# Memory.net
KiCad netlist of a schematic drawn in Altium Designer
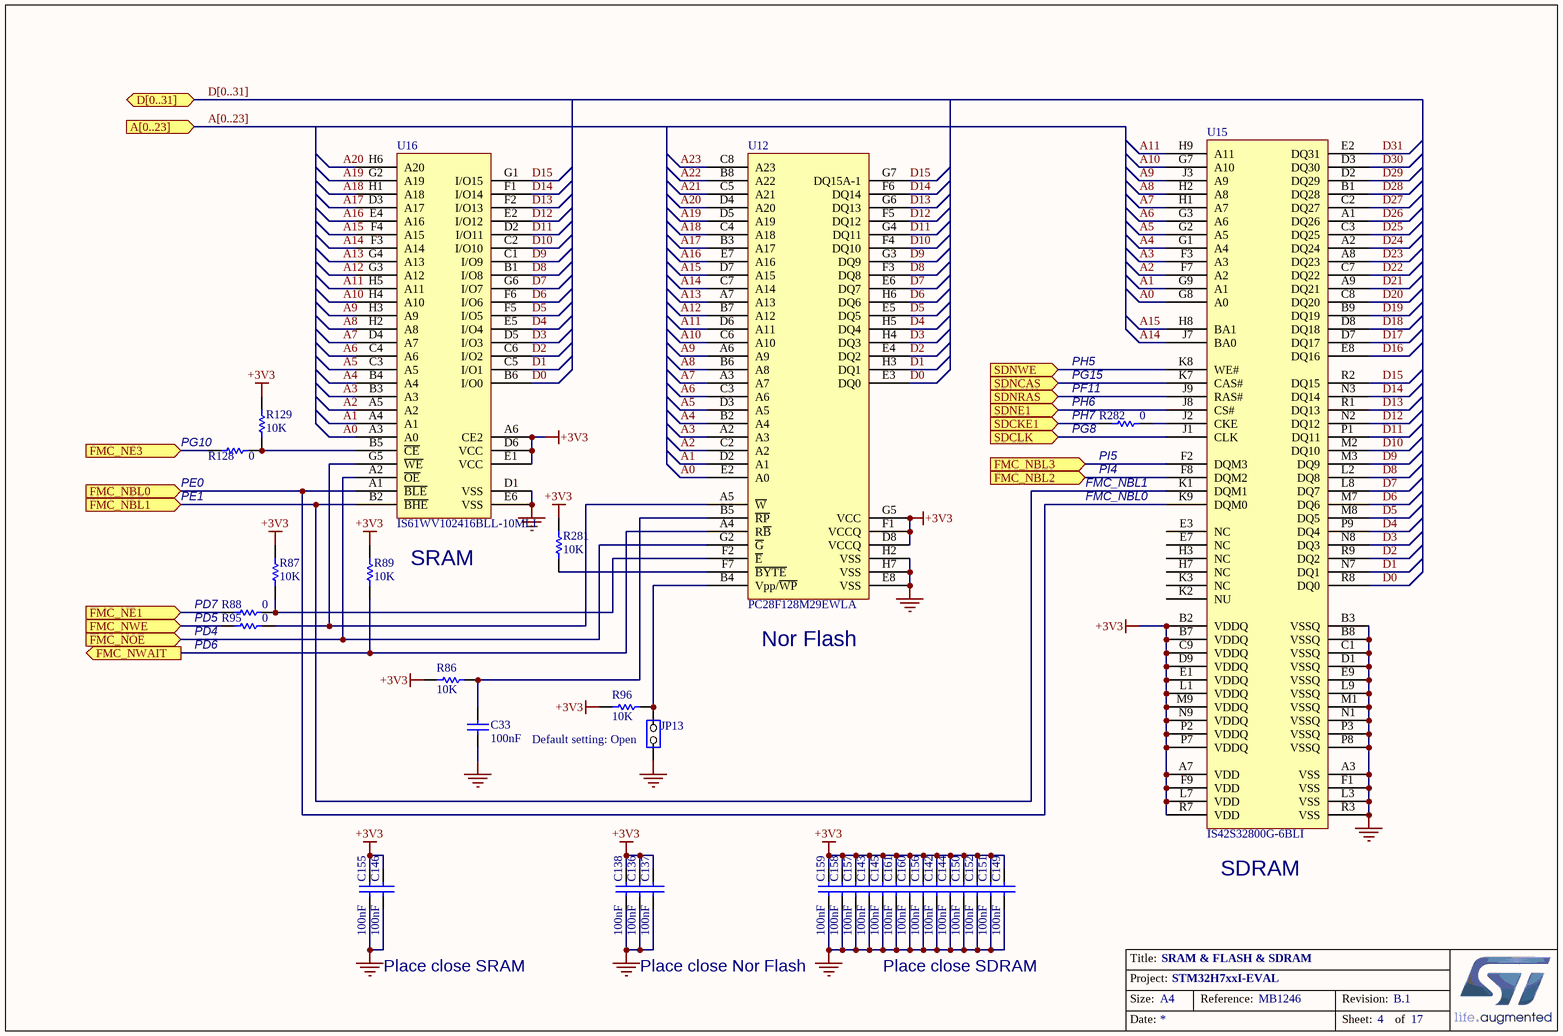
[diagram p0: Memory.SchDoc]

(export (version "E")
  (design (tool "Eeschema 10.0.6"))
  (components
    (comp (ref "C33")
      (value "100nF")
      (footprint "0603C")
      (description "Capacitor")
      (fields (field (name "PUBLISHER") "Altium Limited"))
      (libsource (lib "Miscellaneous Devices") (part "Cap"))
    )
    (comp (ref "C136")
      (value "100nF")
      (footprint "0603C")
      (description "Capacitor")
      (fields (field (name "PUBLISHER") "Altium Limited"))
      (libsource (lib "Miscellaneous Devices") (part "Cap"))
    )
    (comp (ref "C137")
      (value "100nF")
      (footprint "0603C")
      (description "Capacitor")
      (fields (field (name "PUBLISHER") "Altium Limited"))
      (libsource (lib "Miscellaneous Devices") (part "Cap"))
    )
    (comp (ref "C138")
      (value "100nF")
      (footprint "0603C")
      (description "Capacitor")
      (fields (field (name "PUBLISHER") "Altium Limited"))
      (libsource (lib "Miscellaneous Devices") (part "Cap"))
    )
    (comp (ref "C142")
      (value "100nF")
      (footprint "0603C")
      (description "Capacitor")
      (fields (field (name "PUBLISHER") "Altium Limited"))
      (libsource (lib "Miscellaneous Devices") (part "Cap"))
    )
    (comp (ref "C143")
      (value "100nF")
      (footprint "0603C")
      (description "Capacitor")
      (fields (field (name "PUBLISHER") "Altium Limited"))
      (libsource (lib "Miscellaneous Devices") (part "Cap"))
    )
    (comp (ref "C144")
      (value "100nF")
      (footprint "0603C")
      (description "Capacitor")
      (fields (field (name "PUBLISHER") "Altium Limited"))
      (libsource (lib "Miscellaneous Devices") (part "Cap"))
    )
    (comp (ref "C145")
      (value "100nF")
      (footprint "0603C")
      (description "Capacitor")
      (fields (field (name "PUBLISHER") "Altium Limited"))
      (libsource (lib "Miscellaneous Devices") (part "Cap"))
    )
    (comp (ref "C146")
      (value "100nF")
      (footprint "0603C")
      (description "Capacitor")
      (fields (field (name "PUBLISHER") "Altium Limited"))
      (libsource (lib "Miscellaneous Devices") (part "Cap"))
    )
    (comp (ref "C149")
      (value "100nF")
      (footprint "0603C")
      (description "Capacitor")
      (fields (field (name "PUBLISHER") "Altium Limited"))
      (libsource (lib "Miscellaneous Devices") (part "Cap"))
    )
    (comp (ref "C150")
      (value "100nF")
      (footprint "0603C")
      (description "Capacitor")
      (fields (field (name "PUBLISHER") "Altium Limited"))
      (libsource (lib "Miscellaneous Devices") (part "Cap"))
    )
    (comp (ref "C151")
      (value "100nF")
      (footprint "0603C")
      (description "Capacitor")
      (fields (field (name "PUBLISHER") "Altium Limited"))
      (libsource (lib "Miscellaneous Devices") (part "Cap"))
    )
    (comp (ref "C152")
      (value "100nF")
      (footprint "0603C")
      (description "Capacitor")
      (fields (field (name "PUBLISHER") "Altium Limited"))
      (libsource (lib "Miscellaneous Devices") (part "Cap"))
    )
    (comp (ref "C155")
      (value "100nF")
      (footprint "0603C")
      (description "Capacitor")
      (fields (field (name "PUBLISHER") "Altium Limited"))
      (libsource (lib "Miscellaneous Devices") (part "Cap"))
    )
    (comp (ref "C156")
      (value "100nF")
      (footprint "0603C")
      (description "Capacitor")
      (fields (field (name "PUBLISHER") "Altium Limited"))
      (libsource (lib "Miscellaneous Devices") (part "Cap"))
    )
    (comp (ref "C157")
      (value "100nF")
      (footprint "0603C")
      (description "Capacitor")
      (fields (field (name "PUBLISHER") "Altium Limited"))
      (libsource (lib "Miscellaneous Devices") (part "Cap"))
    )
    (comp (ref "C158")
      (value "100nF")
      (footprint "0603C")
      (description "Capacitor")
      (fields (field (name "PUBLISHER") "Altium Limited"))
      (libsource (lib "Miscellaneous Devices") (part "Cap"))
    )
    (comp (ref "C159")
      (value "100nF")
      (footprint "0603C")
      (description "Capacitor")
      (fields (field (name "PUBLISHER") "Altium Limited"))
      (libsource (lib "Miscellaneous Devices") (part "Cap"))
    )
    (comp (ref "C160")
      (value "100nF")
      (footprint "0603C")
      (description "Capacitor")
      (fields (field (name "PUBLISHER") "Altium Limited"))
      (libsource (lib "Miscellaneous Devices") (part "Cap"))
    )
    (comp (ref "C161")
      (value "100nF")
      (footprint "0603C")
      (description "Capacitor")
      (fields (field (name "PUBLISHER") "Altium Limited"))
      (libsource (lib "Miscellaneous Devices") (part "Cap"))
    )
    (comp (ref "JP13") (value "~") (footprint "SIP2") (libsource (lib "*") (part "JP2")))
    (comp (ref "R86")
      (value "10K")
      (footprint "0603R")
      (description "Resistor")
      (fields (field (name "PUBLISHER") "Altium Limited"))
      (libsource (lib "Miscellaneous Devices") (part "Res1"))
    )
    (comp (ref "R87")
      (value "10K")
      (footprint "0603R")
      (description "Resistor")
      (fields (field (name "PUBLISHER") "Altium Limited"))
      (libsource (lib "Miscellaneous Devices") (part "Res1"))
    )
    (comp (ref "R88")
      (value "0")
      (footprint "0603R")
      (description "Resistor")
      (fields (field (name "PUBLISHER") "Altium Limited"))
      (libsource (lib "Miscellaneous Devices") (part "Res1"))
    )
    (comp (ref "R89")
      (value "10K")
      (footprint "0603R")
      (description "Resistor")
      (fields (field (name "PUBLISHER") "Altium Limited"))
      (libsource (lib "Miscellaneous Devices") (part "Res1"))
    )
    (comp (ref "R95")
      (value "0")
      (footprint "0603R")
      (description "Resistor")
      (fields (field (name "PUBLISHER") "Altium Limited"))
      (libsource (lib "Miscellaneous Devices") (part "Res1"))
    )
    (comp (ref "R96")
      (value "10K")
      (footprint "0603R")
      (description "Resistor")
      (fields (field (name "PUBLISHER") "Altium Limited"))
      (libsource (lib "Miscellaneous Devices") (part "Res1"))
    )
    (comp (ref "R128")
      (value "0")
      (footprint "0603R")
      (description "Resistor")
      (fields (field (name "PUBLISHER") "Altium Limited"))
      (libsource (lib "Miscellaneous Devices") (part "Res1"))
    )
    (comp (ref "R129")
      (value "10K")
      (footprint "0603R")
      (description "Resistor")
      (fields (field (name "PUBLISHER") "Altium Limited"))
      (libsource (lib "Miscellaneous Devices") (part "Res1"))
    )
    (comp (ref "R281")
      (value "10K")
      (footprint "0603R")
      (description "Resistor")
      (fields (field (name "PUBLISHER") "Altium Limited"))
      (libsource (lib "Miscellaneous Devices") (part "Res1"))
    )
    (comp (ref "R282")
      (value "0")
      (footprint "0603R")
      (description "Resistor")
      (fields (field (name "PUBLISHER") "Altium Limited"))
      (libsource (lib "Miscellaneous Devices") (part "Res1"))
    )
    (comp (ref "U12")
      (value "PC28F128M29EWLA")
      (footprint "FBGA64_1_11X13")
      (libsource (lib "MB964") (part "M29W128FL70ZA6E"))
    )
    (comp (ref "U15")
      (value "IS42S32800G-6BLI")
      (footprint "FBGA90_0R8_8X13")
      (libsource (lib "mb1045") (part "MT48LC4M32B2B5"))
    )
    (comp (ref "U16")
      (value "IS61WV102416BLL-10MLI")
      (footprint "BGA48_0R75_9X11")
      (libsource (lib "MB901") (part "IS61WV102416BLL-10MLI"))
    )
  )
  (nets
    (net (code "1") (name "+3V3") (class "Default")
      (node (ref "C136") (pin "1") (pinfunction "1_1") (pintype "passive"))
      (node (ref "C137") (pin "1") (pinfunction "1_1") (pintype "passive"))
      (node (ref "C138") (pin "1") (pinfunction "1_1") (pintype "passive"))
      (node (ref "C142") (pin "1") (pinfunction "1_1") (pintype "passive"))
      (node (ref "C143") (pin "1") (pinfunction "1_1") (pintype "passive"))
      (node (ref "C144") (pin "1") (pinfunction "1_1") (pintype "passive"))
      (node (ref "C145") (pin "1") (pinfunction "1_1") (pintype "passive"))
      (node (ref "C146") (pin "1") (pinfunction "1_1") (pintype "passive"))
      (node (ref "C149") (pin "1") (pinfunction "1_1") (pintype "passive"))
      (node (ref "C150") (pin "1") (pinfunction "1_1") (pintype "passive"))
      (node (ref "C151") (pin "1") (pinfunction "1_1") (pintype "passive"))
      (node (ref "C152") (pin "1") (pinfunction "1_1") (pintype "passive"))
      (node (ref "C155") (pin "1") (pinfunction "1_1") (pintype "passive"))
      (node (ref "C156") (pin "1") (pinfunction "1_1") (pintype "passive"))
      (node (ref "C157") (pin "1") (pinfunction "1_1") (pintype "passive"))
      (node (ref "C158") (pin "1") (pinfunction "1_1") (pintype "passive"))
      (node (ref "C159") (pin "1") (pinfunction "1_1") (pintype "passive"))
      (node (ref "C160") (pin "1") (pinfunction "1_1") (pintype "passive"))
      (node (ref "C161") (pin "1") (pinfunction "1_1") (pintype "passive"))
      (node (ref "R129") (pin "2") (pinfunction "2_2") (pintype "passive"))
      (node (ref "R281") (pin "2") (pinfunction "2_2") (pintype "passive"))
      (node (ref "R86") (pin "1") (pinfunction "1_1") (pintype "passive"))
      (node (ref "R87") (pin "2") (pinfunction "2_2") (pintype "passive"))
      (node (ref "R89") (pin "2") (pinfunction "2_2") (pintype "passive"))
      (node (ref "R96") (pin "2") (pinfunction "2_2") (pintype "passive"))
      (node (ref "U12") (pin "D8") (pinfunction "VCCQ_D8") (pintype "passive"))
      (node (ref "U12") (pin "F1") (pinfunction "VCCQ_F1") (pintype "passive"))
      (node (ref "U12") (pin "G5") (pinfunction "VCC_G5") (pintype "passive"))
      (node (ref "U15") (pin "A7") (pinfunction "VDD_A7") (pintype "passive"))
      (node (ref "U15") (pin "B2") (pinfunction "VDDQ_B2") (pintype "passive"))
      (node (ref "U15") (pin "B7") (pinfunction "VDDQ_B7") (pintype "passive"))
      (node (ref "U15") (pin "C9") (pinfunction "VDDQ_C9") (pintype "passive"))
      (node (ref "U15") (pin "D9") (pinfunction "VDDQ_D9") (pintype "passive"))
      (node (ref "U15") (pin "E1") (pinfunction "VDDQ_E1") (pintype "passive"))
      (node (ref "U15") (pin "F9") (pinfunction "VDD_F9") (pintype "passive"))
      (node (ref "U15") (pin "L1") (pinfunction "VDDQ_L1") (pintype "passive"))
      (node (ref "U15") (pin "L7") (pinfunction "VDD_L7") (pintype "passive"))
      (node (ref "U15") (pin "M9") (pinfunction "VDDQ_M9") (pintype "passive"))
      (node (ref "U15") (pin "N9") (pinfunction "VDDQ_N9") (pintype "passive"))
      (node (ref "U15") (pin "P2") (pinfunction "VDDQ_P2") (pintype "passive"))
      (node (ref "U15") (pin "P7") (pinfunction "VDDQ_P7") (pintype "passive"))
      (node (ref "U15") (pin "R7") (pinfunction "VDD_R7") (pintype "passive"))
      (node (ref "U16") (pin "A6") (pinfunction "CE2_A6") (pintype "passive"))
      (node (ref "U16") (pin "D6") (pinfunction "VCC_D6") (pintype "passive"))
      (node (ref "U16") (pin "E1") (pinfunction "VCC_E1") (pintype "passive"))
    )
    (net (code "2") (name "/A0") (class "Default")
      (node (ref "U12") (pin "E2") (pinfunction "A0_E2") (pintype "passive"))
      (node (ref "U15") (pin "G8") (pinfunction "A0_G8") (pintype "passive"))
      (node (ref "U16") (pin "A3") (pinfunction "A0_A3") (pintype "passive"))
    )
    (net (code "3") (name "/A1") (class "Default")
      (node (ref "U12") (pin "D2") (pinfunction "A1_D2") (pintype "passive"))
      (node (ref "U15") (pin "G9") (pinfunction "A1_G9") (pintype "passive"))
      (node (ref "U16") (pin "A4") (pinfunction "A1_A4") (pintype "passive"))
    )
    (net (code "4") (name "/A2") (class "Default")
      (node (ref "U12") (pin "C2") (pinfunction "A2_C2") (pintype "passive"))
      (node (ref "U15") (pin "F7") (pinfunction "A2_F7") (pintype "passive"))
      (node (ref "U16") (pin "A5") (pinfunction "A2_A5") (pintype "passive"))
    )
    (net (code "5") (name "/A3") (class "Default")
      (node (ref "U12") (pin "A2") (pinfunction "A3_A2") (pintype "passive"))
      (node (ref "U15") (pin "F3") (pinfunction "A3_F3") (pintype "passive"))
      (node (ref "U16") (pin "B3") (pinfunction "A3_B3") (pintype "passive"))
    )
    (net (code "6") (name "/A4") (class "Default")
      (node (ref "U12") (pin "B2") (pinfunction "A4_B2") (pintype "passive"))
      (node (ref "U15") (pin "G1") (pinfunction "A4_G1") (pintype "passive"))
      (node (ref "U16") (pin "B4") (pinfunction "A4_B4") (pintype "passive"))
    )
    (net (code "7") (name "/A5") (class "Default")
      (node (ref "U12") (pin "D3") (pinfunction "A5_D3") (pintype "passive"))
      (node (ref "U15") (pin "G2") (pinfunction "A5_G2") (pintype "passive"))
      (node (ref "U16") (pin "C3") (pinfunction "A5_C3") (pintype "passive"))
    )
    (net (code "8") (name "/A6") (class "Default")
      (node (ref "U12") (pin "C3") (pinfunction "A6_C3") (pintype "passive"))
      (node (ref "U15") (pin "G3") (pinfunction "A6_G3") (pintype "passive"))
      (node (ref "U16") (pin "C4") (pinfunction "A6_C4") (pintype "passive"))
    )
    (net (code "9") (name "/A7") (class "Default")
      (node (ref "U12") (pin "A3") (pinfunction "A7_A3") (pintype "passive"))
      (node (ref "U15") (pin "H1") (pinfunction "A7_H1") (pintype "passive"))
      (node (ref "U16") (pin "D4") (pinfunction "A7_D4") (pintype "passive"))
    )
    (net (code "10") (name "/A8") (class "Default")
      (node (ref "U12") (pin "B6") (pinfunction "A8_B6") (pintype "passive"))
      (node (ref "U15") (pin "H2") (pinfunction "A8_H2") (pintype "passive"))
      (node (ref "U16") (pin "H2") (pinfunction "A8_H2") (pintype "passive"))
    )
    (net (code "11") (name "/A9") (class "Default")
      (node (ref "U12") (pin "A6") (pinfunction "A9_A6") (pintype "passive"))
      (node (ref "U15") (pin "J3") (pinfunction "A9_J3") (pintype "passive"))
      (node (ref "U16") (pin "H3") (pinfunction "A9_H3") (pintype "passive"))
    )
    (net (code "12") (name "/A10") (class "Default")
      (node (ref "U12") (pin "C6") (pinfunction "A10_C6") (pintype "passive"))
      (node (ref "U15") (pin "G7") (pinfunction "A10_G7") (pintype "passive"))
      (node (ref "U16") (pin "H4") (pinfunction "A10_H4") (pintype "passive"))
    )
    (net (code "13") (name "/A11") (class "Default")
      (node (ref "U12") (pin "D6") (pinfunction "A11_D6") (pintype "passive"))
      (node (ref "U15") (pin "H9") (pinfunction "A11_H9") (pintype "passive"))
      (node (ref "U16") (pin "H5") (pinfunction "A11_H5") (pintype "passive"))
    )
    (net (code "14") (name "/A12") (class "Default")
      (node (ref "U12") (pin "B7") (pinfunction "A12_B7") (pintype "passive"))
      (node (ref "U16") (pin "G3") (pinfunction "A12_G3") (pintype "passive"))
    )
    (net (code "15") (name "/A13") (class "Default")
      (node (ref "U12") (pin "A7") (pinfunction "A13_A7") (pintype "passive"))
      (node (ref "U16") (pin "G4") (pinfunction "A13_G4") (pintype "passive"))
    )
    (net (code "16") (name "/A14") (class "Default")
      (node (ref "U12") (pin "C7") (pinfunction "A14_C7") (pintype "passive"))
      (node (ref "U15") (pin "J7") (pinfunction "BA0_J7") (pintype "passive"))
      (node (ref "U16") (pin "F3") (pinfunction "A14_F3") (pintype "passive"))
    )
    (net (code "17") (name "/A15") (class "Default")
      (node (ref "U12") (pin "D7") (pinfunction "A15_D7") (pintype "passive"))
      (node (ref "U15") (pin "H8") (pinfunction "BA1_H8") (pintype "passive"))
      (node (ref "U16") (pin "F4") (pinfunction "A15_F4") (pintype "passive"))
    )
    (net (code "18") (name "/A16") (class "Default")
      (node (ref "U12") (pin "E7") (pinfunction "A16_E7") (pintype "passive"))
      (node (ref "U16") (pin "E4") (pinfunction "A16_E4") (pintype "passive"))
    )
    (net (code "19") (name "/A17") (class "Default")
      (node (ref "U12") (pin "B3") (pinfunction "A17_B3") (pintype "passive"))
      (node (ref "U16") (pin "D3") (pinfunction "A17_D3") (pintype "passive"))
    )
    (net (code "20") (name "/A18") (class "Default")
      (node (ref "U12") (pin "C4") (pinfunction "A18_C4") (pintype "passive"))
      (node (ref "U16") (pin "H1") (pinfunction "A18_H1") (pintype "passive"))
    )
    (net (code "21") (name "/A19") (class "Default")
      (node (ref "U12") (pin "D5") (pinfunction "A19_D5") (pintype "passive"))
      (node (ref "U16") (pin "G2") (pinfunction "A19_G2") (pintype "passive"))
    )
    (net (code "22") (name "/A20") (class "Default")
      (node (ref "U12") (pin "D4") (pinfunction "A20_D4") (pintype "passive"))
      (node (ref "U16") (pin "H6") (pinfunction "A20_H6") (pintype "passive"))
    )
    (net (code "23") (name "/A21") (class "Default")
      (node (ref "U12") (pin "C5") (pinfunction "A21_C5") (pintype "passive"))
    )
    (net (code "24") (name "/A22") (class "Default")
      (node (ref "U12") (pin "B8") (pinfunction "A22_B8") (pintype "passive"))
    )
    (net (code "25") (name "/A23") (class "Default")
      (node (ref "U12") (pin "C8") (pinfunction "A23_C8") (pintype "passive"))
    )
    (net (code "27") (name "/D0") (class "Default")
      (node (ref "U12") (pin "E3") (pinfunction "DQ0_E3") (pintype "passive"))
      (node (ref "U15") (pin "R8") (pinfunction "DQ0_R8") (pintype "passive"))
      (node (ref "U16") (pin "B6") (pinfunction "I/O0_B6") (pintype "passive"))
    )
    (net (code "28") (name "/D1") (class "Default")
      (node (ref "U12") (pin "H3") (pinfunction "DQ1_H3") (pintype "passive"))
      (node (ref "U15") (pin "N7") (pinfunction "DQ1_N7") (pintype "passive"))
      (node (ref "U16") (pin "C5") (pinfunction "I/O1_C5") (pintype "passive"))
    )
    (net (code "29") (name "/D2") (class "Default")
      (node (ref "U12") (pin "E4") (pinfunction "DQ2_E4") (pintype "passive"))
      (node (ref "U15") (pin "R9") (pinfunction "DQ2_R9") (pintype "passive"))
      (node (ref "U16") (pin "C6") (pinfunction "I/O2_C6") (pintype "passive"))
    )
    (net (code "30") (name "/D3") (class "Default")
      (node (ref "U12") (pin "H4") (pinfunction "DQ3_H4") (pintype "passive"))
      (node (ref "U15") (pin "N8") (pinfunction "DQ3_N8") (pintype "passive"))
      (node (ref "U16") (pin "D5") (pinfunction "I/O3_D5") (pintype "passive"))
    )
    (net (code "31") (name "/D4") (class "Default")
      (node (ref "U12") (pin "H5") (pinfunction "DQ4_H5") (pintype "passive"))
      (node (ref "U15") (pin "P9") (pinfunction "DQ4_P9") (pintype "passive"))
      (node (ref "U16") (pin "E5") (pinfunction "I/O4_E5") (pintype "passive"))
    )
    (net (code "32") (name "/D5") (class "Default")
      (node (ref "U12") (pin "E5") (pinfunction "DQ5_E5") (pintype "passive"))
      (node (ref "U15") (pin "M8") (pinfunction "DQ5_M8") (pintype "passive"))
      (node (ref "U16") (pin "F5") (pinfunction "I/O5_F5") (pintype "passive"))
    )
    (net (code "33") (name "/D6") (class "Default")
      (node (ref "U12") (pin "H6") (pinfunction "DQ6_H6") (pintype "passive"))
      (node (ref "U15") (pin "M7") (pinfunction "DQ6_M7") (pintype "passive"))
      (node (ref "U16") (pin "F6") (pinfunction "I/O6_F6") (pintype "passive"))
    )
    (net (code "34") (name "/D7") (class "Default")
      (node (ref "U12") (pin "E6") (pinfunction "DQ7_E6") (pintype "passive"))
      (node (ref "U15") (pin "L8") (pinfunction "DQ7_L8") (pintype "passive"))
      (node (ref "U16") (pin "G6") (pinfunction "I/O7_G6") (pintype "passive"))
    )
    (net (code "35") (name "/D8") (class "Default")
      (node (ref "U12") (pin "F3") (pinfunction "DQ8_F3") (pintype "passive"))
      (node (ref "U15") (pin "L2") (pinfunction "DQ8_L2") (pintype "passive"))
      (node (ref "U16") (pin "B1") (pinfunction "I/O8_B1") (pintype "passive"))
    )
    (net (code "36") (name "/D9") (class "Default")
      (node (ref "U12") (pin "G3") (pinfunction "DQ9_G3") (pintype "passive"))
      (node (ref "U15") (pin "M3") (pinfunction "DQ9_M3") (pintype "passive"))
      (node (ref "U16") (pin "C1") (pinfunction "I/O9_C1") (pintype "passive"))
    )
    (net (code "37") (name "/D10") (class "Default")
      (node (ref "U12") (pin "F4") (pinfunction "DQ10_F4") (pintype "passive"))
      (node (ref "U15") (pin "M2") (pinfunction "DQ10_M2") (pintype "passive"))
      (node (ref "U16") (pin "C2") (pinfunction "I/O10_C2") (pintype "passive"))
    )
    (net (code "38") (name "/D11") (class "Default")
      (node (ref "U12") (pin "G4") (pinfunction "DQ11_G4") (pintype "passive"))
      (node (ref "U15") (pin "P1") (pinfunction "DQ11_P1") (pintype "passive"))
      (node (ref "U16") (pin "D2") (pinfunction "I/O11_D2") (pintype "passive"))
    )
    (net (code "39") (name "/D12") (class "Default")
      (node (ref "U12") (pin "F5") (pinfunction "DQ12_F5") (pintype "passive"))
      (node (ref "U15") (pin "N2") (pinfunction "DQ12_N2") (pintype "passive"))
      (node (ref "U16") (pin "E2") (pinfunction "I/O12_E2") (pintype "passive"))
    )
    (net (code "40") (name "/D13") (class "Default")
      (node (ref "U12") (pin "G6") (pinfunction "DQ13_G6") (pintype "passive"))
      (node (ref "U15") (pin "R1") (pinfunction "DQ13_R1") (pintype "passive"))
      (node (ref "U16") (pin "F2") (pinfunction "I/O13_F2") (pintype "passive"))
    )
    (net (code "41") (name "/D14") (class "Default")
      (node (ref "U12") (pin "F6") (pinfunction "DQ14_F6") (pintype "passive"))
      (node (ref "U15") (pin "N3") (pinfunction "DQ14_N3") (pintype "passive"))
      (node (ref "U16") (pin "F1") (pinfunction "I/O14_F1") (pintype "passive"))
    )
    (net (code "42") (name "/D15") (class "Default")
      (node (ref "U12") (pin "G7") (pinfunction "DQ15A-1_G7") (pintype "passive"))
      (node (ref "U15") (pin "R2") (pinfunction "DQ15_R2") (pintype "passive"))
      (node (ref "U16") (pin "G1") (pinfunction "I/O15_G1") (pintype "passive"))
    )
    (net (code "43") (name "/D16") (class "Default")
      (node (ref "U15") (pin "E8") (pinfunction "DQ16_E8") (pintype "passive"))
    )
    (net (code "44") (name "/D17") (class "Default")
      (node (ref "U15") (pin "D7") (pinfunction "DQ17_D7") (pintype "passive"))
    )
    (net (code "45") (name "/D18") (class "Default")
      (node (ref "U15") (pin "D8") (pinfunction "DQ18_D8") (pintype "passive"))
    )
    (net (code "46") (name "/D19") (class "Default")
      (node (ref "U15") (pin "B9") (pinfunction "DQ19_B9") (pintype "passive"))
    )
    (net (code "47") (name "/D20") (class "Default")
      (node (ref "U15") (pin "C8") (pinfunction "DQ20_C8") (pintype "passive"))
    )
    (net (code "48") (name "/D21") (class "Default")
      (node (ref "U15") (pin "A9") (pinfunction "DQ21_A9") (pintype "passive"))
    )
    (net (code "49") (name "/D22") (class "Default")
      (node (ref "U15") (pin "C7") (pinfunction "DQ22_C7") (pintype "passive"))
    )
    (net (code "50") (name "/D23") (class "Default")
      (node (ref "U15") (pin "A8") (pinfunction "DQ23_A8") (pintype "passive"))
    )
    (net (code "51") (name "/D24") (class "Default")
      (node (ref "U15") (pin "A2") (pinfunction "DQ24_A2") (pintype "passive"))
    )
    (net (code "52") (name "/D25") (class "Default")
      (node (ref "U15") (pin "C3") (pinfunction "DQ25_C3") (pintype "passive"))
    )
    (net (code "53") (name "/D26") (class "Default")
      (node (ref "U15") (pin "A1") (pinfunction "DQ26_A1") (pintype "passive"))
    )
    (net (code "54") (name "/D27") (class "Default")
      (node (ref "U15") (pin "C2") (pinfunction "DQ27_C2") (pintype "passive"))
    )
    (net (code "55") (name "/D28") (class "Default")
      (node (ref "U15") (pin "B1") (pinfunction "DQ28_B1") (pintype "passive"))
    )
    (net (code "56") (name "/D29") (class "Default")
      (node (ref "U15") (pin "D2") (pinfunction "DQ29_D2") (pintype "passive"))
    )
    (net (code "57") (name "/D30") (class "Default")
      (node (ref "U15") (pin "D3") (pinfunction "DQ30_D3") (pintype "passive"))
    )
    (net (code "58") (name "/D31") (class "Default")
      (node (ref "U15") (pin "E2") (pinfunction "DQ31_E2") (pintype "passive"))
    )
    (net (code "60") (name "/FMC_NBL0") (class "Default")
      (node (ref "U15") (pin "K9") (pinfunction "DQM0_K9") (pintype "passive"))
      (node (ref "U16") (pin "A1") (pinfunction "~{BLE}_A1") (pintype "passive"))
    )
    (net (code "61") (name "/FMC_NBL1") (class "Default")
      (node (ref "U15") (pin "K1") (pinfunction "DQM1_K1") (pintype "passive"))
      (node (ref "U16") (pin "B2") (pinfunction "~{BHE}_B2") (pintype "passive"))
    )
    (net (code "62") (name "/FMC_NBL2") (class "Default")
      (node (ref "U15") (pin "F8") (pinfunction "DQM2_F8") (pintype "passive"))
    )
    (net (code "63") (name "/FMC_NBL3") (class "Default")
      (node (ref "U15") (pin "F2") (pinfunction "DQM3_F2") (pintype "passive"))
    )
    (net (code "64") (name "/FMC_NE1") (class "Default")
      (node (ref "R88") (pin "2") (pinfunction "2_2") (pintype "passive"))
    )
    (net (code "65") (name "/FMC_NE3") (class "Default")
      (node (ref "R128") (pin "2") (pinfunction "2_2") (pintype "passive"))
    )
    (net (code "66") (name "/FMC_NOE") (class "Default")
      (node (ref "U12") (pin "G2") (pinfunction "~{G}_G2") (pintype "passive"))
      (node (ref "U16") (pin "A2") (pinfunction "~{OE}_A2") (pintype "passive"))
    )
    (net (code "67") (name "/FMC_NWAIT") (class "Default")
      (node (ref "R89") (pin "1") (pinfunction "1_1") (pintype "passive"))
      (node (ref "U12") (pin "A4") (pinfunction "R~{B}_A4") (pintype "passive"))
    )
    (net (code "68") (name "/FMC_NWE") (class "Default")
      (node (ref "R95") (pin "2") (pinfunction "2_2") (pintype "passive"))
    )
    (net (code "69") (name "/SDCKE1") (class "Default")
      (node (ref "R282") (pin "2") (pinfunction "2_2") (pintype "passive"))
    )
    (net (code "70") (name "/SDCLK") (class "Default")
      (node (ref "U15") (pin "J1") (pinfunction "CLK_J1") (pintype "passive"))
    )
    (net (code "71") (name "/SDNCAS") (class "Default")
      (node (ref "U15") (pin "K7") (pinfunction "CAS#_K7") (pintype "passive"))
    )
    (net (code "72") (name "/SDNE1") (class "Default")
      (node (ref "U15") (pin "J8") (pinfunction "CS#_J8") (pintype "passive"))
    )
    (net (code "73") (name "/SDNRAS") (class "Default")
      (node (ref "U15") (pin "J9") (pinfunction "RAS#_J9") (pintype "passive"))
    )
    (net (code "74") (name "/SDNWE") (class "Default")
      (node (ref "U15") (pin "K8") (pinfunction "WE#_K8") (pintype "passive"))
    )
    (net (code "75") (name "GND") (class "Default")
      (node (ref "C136") (pin "2") (pinfunction "2_2") (pintype "passive"))
      (node (ref "C137") (pin "2") (pinfunction "2_2") (pintype "passive"))
      (node (ref "C138") (pin "2") (pinfunction "2_2") (pintype "passive"))
      (node (ref "C142") (pin "2") (pinfunction "2_2") (pintype "passive"))
      (node (ref "C143") (pin "2") (pinfunction "2_2") (pintype "passive"))
      (node (ref "C144") (pin "2") (pinfunction "2_2") (pintype "passive"))
      (node (ref "C145") (pin "2") (pinfunction "2_2") (pintype "passive"))
      (node (ref "C146") (pin "2") (pinfunction "2_2") (pintype "passive"))
      (node (ref "C149") (pin "2") (pinfunction "2_2") (pintype "passive"))
      (node (ref "C150") (pin "2") (pinfunction "2_2") (pintype "passive"))
      (node (ref "C151") (pin "2") (pinfunction "2_2") (pintype "passive"))
      (node (ref "C152") (pin "2") (pinfunction "2_2") (pintype "passive"))
      (node (ref "C155") (pin "2") (pinfunction "2_2") (pintype "passive"))
      (node (ref "C156") (pin "2") (pinfunction "2_2") (pintype "passive"))
      (node (ref "C157") (pin "2") (pinfunction "2_2") (pintype "passive"))
      (node (ref "C158") (pin "2") (pinfunction "2_2") (pintype "passive"))
      (node (ref "C159") (pin "2") (pinfunction "2_2") (pintype "passive"))
      (node (ref "C160") (pin "2") (pinfunction "2_2") (pintype "passive"))
      (node (ref "C161") (pin "2") (pinfunction "2_2") (pintype "passive"))
      (node (ref "C33") (pin "2") (pinfunction "2_2") (pintype "passive"))
      (node (ref "JP13") (pin "1") (pinfunction "COMMON_1") (pintype "passive"))
      (node (ref "U12") (pin "E8") (pinfunction "VSS_E8") (pintype "passive"))
      (node (ref "U12") (pin "H2") (pinfunction "VSS_H2") (pintype "passive"))
      (node (ref "U12") (pin "H7") (pinfunction "VSS_H7") (pintype "passive"))
      (node (ref "U15") (pin "A3") (pinfunction "VSS_A3") (pintype "passive"))
      (node (ref "U15") (pin "B3") (pinfunction "VSSQ_B3") (pintype "passive"))
      (node (ref "U15") (pin "B8") (pinfunction "VSSQ_B8") (pintype "passive"))
      (node (ref "U15") (pin "C1") (pinfunction "VSSQ_C1") (pintype "passive"))
      (node (ref "U15") (pin "D1") (pinfunction "VSSQ_D1") (pintype "passive"))
      (node (ref "U15") (pin "E9") (pinfunction "VSSQ_E9") (pintype "passive"))
      (node (ref "U15") (pin "F1") (pinfunction "VSS_F1") (pintype "passive"))
      (node (ref "U15") (pin "L3") (pinfunction "VSS_L3") (pintype "passive"))
      (node (ref "U15") (pin "L9") (pinfunction "VSSQ_L9") (pintype "passive"))
      (node (ref "U15") (pin "M1") (pinfunction "VSSQ_M1") (pintype "passive"))
      (node (ref "U15") (pin "N1") (pinfunction "VSSQ_N1") (pintype "passive"))
      (node (ref "U15") (pin "P3") (pinfunction "VSSQ_P3") (pintype "passive"))
      (node (ref "U15") (pin "P8") (pinfunction "VSSQ_P8") (pintype "passive"))
      (node (ref "U15") (pin "R3") (pinfunction "VSS_R3") (pintype "passive"))
      (node (ref "U16") (pin "D1") (pinfunction "VSS_D1") (pintype "passive"))
      (node (ref "U16") (pin "E6") (pinfunction "VSS_E6") (pintype "passive"))
    )
    (net (code "76") (name "Net-(JP13-NO)") (class "Default")
      (node (ref "JP13") (pin "2") (pinfunction "NO_2") (pintype "passive"))
      (node (ref "R96") (pin "1") (pinfunction "1_1") (pintype "passive"))
      (node (ref "U12") (pin "B4") (pinfunction "Vpp/~{WP}_B4") (pintype "passive"))
    )
    (net (code "77") (name "Net-(U12-~{BYTE})") (class "Default")
      (node (ref "R281") (pin "1") (pinfunction "1_1") (pintype "passive"))
      (node (ref "U12") (pin "F7") (pinfunction "~{BYTE}_F7") (pintype "passive"))
    )
    (net (code "78") (name "Net-(U12-~{E})") (class "Default")
      (node (ref "R87") (pin "1") (pinfunction "1_1") (pintype "passive"))
      (node (ref "R88") (pin "1") (pinfunction "1_1") (pintype "passive"))
      (node (ref "U12") (pin "F2") (pinfunction "~{E}_F2") (pintype "passive"))
    )
    (net (code "79") (name "Net-(U12-~{RP})") (class "Default")
      (node (ref "C33") (pin "1") (pinfunction "1_1") (pintype "passive"))
      (node (ref "R86") (pin "2") (pinfunction "2_2") (pintype "passive"))
      (node (ref "U12") (pin "B5") (pinfunction "~{RP}_B5") (pintype "passive"))
    )
    (net (code "80") (name "Net-(U12-~{W})") (class "Default")
      (node (ref "R95") (pin "1") (pinfunction "1_1") (pintype "passive"))
      (node (ref "U12") (pin "A5") (pinfunction "~{W}_A5") (pintype "passive"))
      (node (ref "U16") (pin "G5") (pinfunction "~{WE}_G5") (pintype "passive"))
    )
    (net (code "81") (name "Net-(U15-CKE)") (class "Default")
      (node (ref "R282") (pin "1") (pinfunction "1_1") (pintype "passive"))
      (node (ref "U15") (pin "J2") (pinfunction "CKE_J2") (pintype "passive"))
    )
    (net (code "82") (name "Net-(U16-~{CE})") (class "Default")
      (node (ref "R128") (pin "1") (pinfunction "1_1") (pintype "passive"))
      (node (ref "R129") (pin "1") (pinfunction "1_1") (pintype "passive"))
      (node (ref "U16") (pin "B5") (pinfunction "~{CE}_B5") (pintype "passive"))
    )
    (net (code "83") (name "unconnected-(U15-NC-PadE3)") (class "Default")
      (node (ref "U15") (pin "E3") (pinfunction "NC_E3") (pintype "passive"))
    )
    (net (code "84") (name "unconnected-(U15-NC-PadE7)") (class "Default")
      (node (ref "U15") (pin "E7") (pinfunction "NC_E7") (pintype "passive"))
    )
    (net (code "85") (name "unconnected-(U15-NC-PadH3)") (class "Default")
      (node (ref "U15") (pin "H3") (pinfunction "NC_H3") (pintype "passive"))
    )
    (net (code "86") (name "unconnected-(U15-NC-PadH7)") (class "Default")
      (node (ref "U15") (pin "H7") (pinfunction "NC_H7") (pintype "passive"))
    )
    (net (code "87") (name "unconnected-(U15-NC-PadK3)") (class "Default")
      (node (ref "U15") (pin "K3") (pinfunction "NC_K3") (pintype "passive"))
    )
    (net (code "88") (name "unconnected-(U15-NU-PadK2)") (class "Default")
      (node (ref "U15") (pin "K2") (pinfunction "NU_K2") (pintype "passive"))
    )
  )
)
